# LEDBLINKING_AstableMultiVbrator.net
KiCad netlist of a schematic drawn in Altium Designer
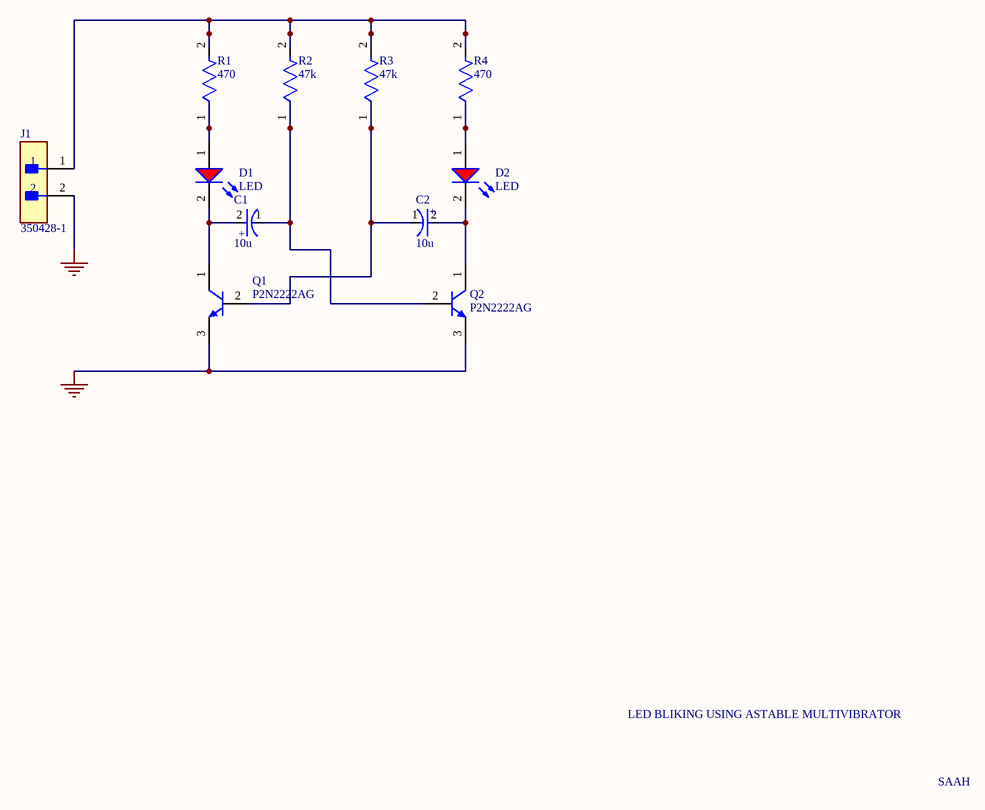
[diagram p0: LEDBLINKING(AstableMultiVbrator).SchDoc]

(export (version "E")
  (design (tool "Eeschema 10.0.6"))
  (components
    (comp (ref "C1")
      (value "10u")
      (footprint "FP-RAD-TH-D_12_5_0_5-L_20-MFG")
      (description "Aluminum Electrolytic Capacitors (Radial Lead Type) 10uF ±20% 450V")
      (fields (field (name "TOLERANCE") "20%") (field (name "VOLTAGE") "450V"))
      (libsource (lib "Altium Content Vault") (part "a00bbbee19879c290e62620ae7e47b1"))
    )
    (comp (ref "C2")
      (value "10u")
      (footprint "FP-RAD-TH-D_12_5_0_5-L_20-MFG")
      (description "Aluminum Electrolytic Capacitors (Radial Lead Type) 10uF ±20% 450V")
      (fields (field (name "TOLERANCE") "20%") (field (name "VOLTAGE") "450V"))
      (libsource (lib "Altium Content Vault") (part "a00bbbee19879c290e62620ae7e47b1"))
    )
    (comp (ref "D1")
      (value "LED")
      (footprint "WL-TMRC_D5.9H8.7")
      (description "151051SS04000 WL-TMRC THT Mono-color Round Color")
      (libsource (lib "Altium Content Vault") (part "LED_Red_1A-2K"))
    )
    (comp (ref "D2")
      (value "LED")
      (footprint "WL-TMRC_D5.9H8.7")
      (description "151051SS04000 WL-TMRC THT Mono-color Round Color")
      (libsource (lib "Altium Content Vault") (part "LED_Red_1A-2K"))
    )
    (comp (ref "J1")
      (value "350428-1")
      (footprint "FP-350428-1-MFG")
      (description "CONN HEADER VERT 2POS 6.35MM")
      (fields
        (field (name "OCTOPART") "https://octopart.com/350428-1-te+connectivity-46505355")
        (field (name "MANUFACTURER") "TE Connectivity")
      )
      (libsource (lib "Altium Content Vault") (part "3bc925449376181038e59eaffc5286c"))
    )
    (comp (ref "Q1")
      (value "P2N2222AG")
      (footprint "ONSC-TO-92-3-29-11")
      (description "Amplifier Transistor, NPN Silicon, 3-Pin TO-92, Pb-Free, Bulk Box")
      (fields (field (name "MANUFACTURER") "On Semiconductor"))
      (libsource (lib "Altium Content Vault") (part "ONSC-NPN-C1B2E3-3"))
    )
    (comp (ref "Q2")
      (value "P2N2222AG")
      (footprint "ONSC-TO-92-3-29-11")
      (description "Amplifier Transistor, NPN Silicon, 3-Pin TO-92, Pb-Free, Bulk Box")
      (fields (field (name "MANUFACTURER") "On Semiconductor"))
      (libsource (lib "Altium Content Vault") (part "ONSC-NPN-C1B2E3-3"))
    )
    (comp (ref "R1")
      (value "470")
      (footprint "FP-CF14-MFG")
      (description "RES 7.5K OHM 1/4W 5% AXIAL")
      (fields (field (name "TOLERANCE") "5%"))
      (libsource (lib "Altium Content Vault") (part "1029c3af85768c4190bb7ad29bc67b5"))
    )
    (comp (ref "R2")
      (value "47k")
      (footprint "FP-CF14-MFG")
      (description "RES 7.5K OHM 1/4W 5% AXIAL")
      (fields (field (name "TOLERANCE") "5%"))
      (libsource (lib "Altium Content Vault") (part "1029c3af85768c4190bb7ad29bc67b5"))
    )
    (comp (ref "R3")
      (value "47k")
      (footprint "FP-CF14-MFG")
      (description "RES 7.5K OHM 1/4W 5% AXIAL")
      (fields (field (name "TOLERANCE") "5%"))
      (libsource (lib "Altium Content Vault") (part "1029c3af85768c4190bb7ad29bc67b5"))
    )
    (comp (ref "R4")
      (value "470")
      (footprint "FP-CF14-MFG")
      (description "RES 7.5K OHM 1/4W 5% AXIAL")
      (fields (field (name "TOLERANCE") "5%"))
      (libsource (lib "Altium Content Vault") (part "1029c3af85768c4190bb7ad29bc67b5"))
    )
  )
  (nets
    (net (code "1") (name "GND") (class "Default")
      (node (ref "J1") (pin "2") (pinfunction "2_2") (pintype "passive"))
      (node (ref "Q1") (pin "3") (pinfunction "E_3") (pintype "passive"))
      (node (ref "Q2") (pin "3") (pinfunction "E_3") (pintype "passive"))
    )
    (net (code "2") (name "Net-(C1-A)") (class "Default")
      (node (ref "C1") (pin "2") (pinfunction "A_2") (pintype "passive"))
      (node (ref "D1") (pin "2") (pinfunction "K_2") (pintype "passive"))
      (node (ref "Q1") (pin "1") (pinfunction "C_1") (pintype "passive"))
    )
    (net (code "3") (name "Net-(C1-C)") (class "Default")
      (node (ref "C1") (pin "1") (pinfunction "C_1") (pintype "passive"))
      (node (ref "Q2") (pin "2") (pinfunction "B_2") (pintype "passive"))
      (node (ref "R2") (pin "1") (pinfunction "1_1") (pintype "passive"))
    )
    (net (code "4") (name "Net-(C2-A)") (class "Default")
      (node (ref "C2") (pin "2") (pinfunction "A_2") (pintype "passive"))
      (node (ref "D2") (pin "2") (pinfunction "K_2") (pintype "passive"))
      (node (ref "Q2") (pin "1") (pinfunction "C_1") (pintype "passive"))
    )
    (net (code "5") (name "Net-(C2-C)") (class "Default")
      (node (ref "C2") (pin "1") (pinfunction "C_1") (pintype "passive"))
      (node (ref "Q1") (pin "2") (pinfunction "B_2") (pintype "passive"))
      (node (ref "R3") (pin "1") (pinfunction "1_1") (pintype "passive"))
    )
    (net (code "6") (name "Net-(D1-A)") (class "Default")
      (node (ref "D1") (pin "1") (pinfunction "A_1") (pintype "passive"))
      (node (ref "R1") (pin "1") (pinfunction "1_1") (pintype "passive"))
    )
    (net (code "7") (name "Net-(D2-A)") (class "Default")
      (node (ref "D2") (pin "1") (pinfunction "A_1") (pintype "passive"))
      (node (ref "R4") (pin "1") (pinfunction "1_1") (pintype "passive"))
    )
    (net (code "8") (name "Net-(J1-Pad1)") (class "Default")
      (node (ref "J1") (pin "1") (pinfunction "1_1") (pintype "passive"))
      (node (ref "R1") (pin "2") (pinfunction "2_2") (pintype "passive"))
      (node (ref "R2") (pin "2") (pinfunction "2_2") (pintype "passive"))
      (node (ref "R3") (pin "2") (pinfunction "2_2") (pintype "passive"))
      (node (ref "R4") (pin "2") (pinfunction "2_2") (pintype "passive"))
    )
  )
)
